# Angra_v_1_0.net
KiCad netlist of a schematic drawn in EAGLE
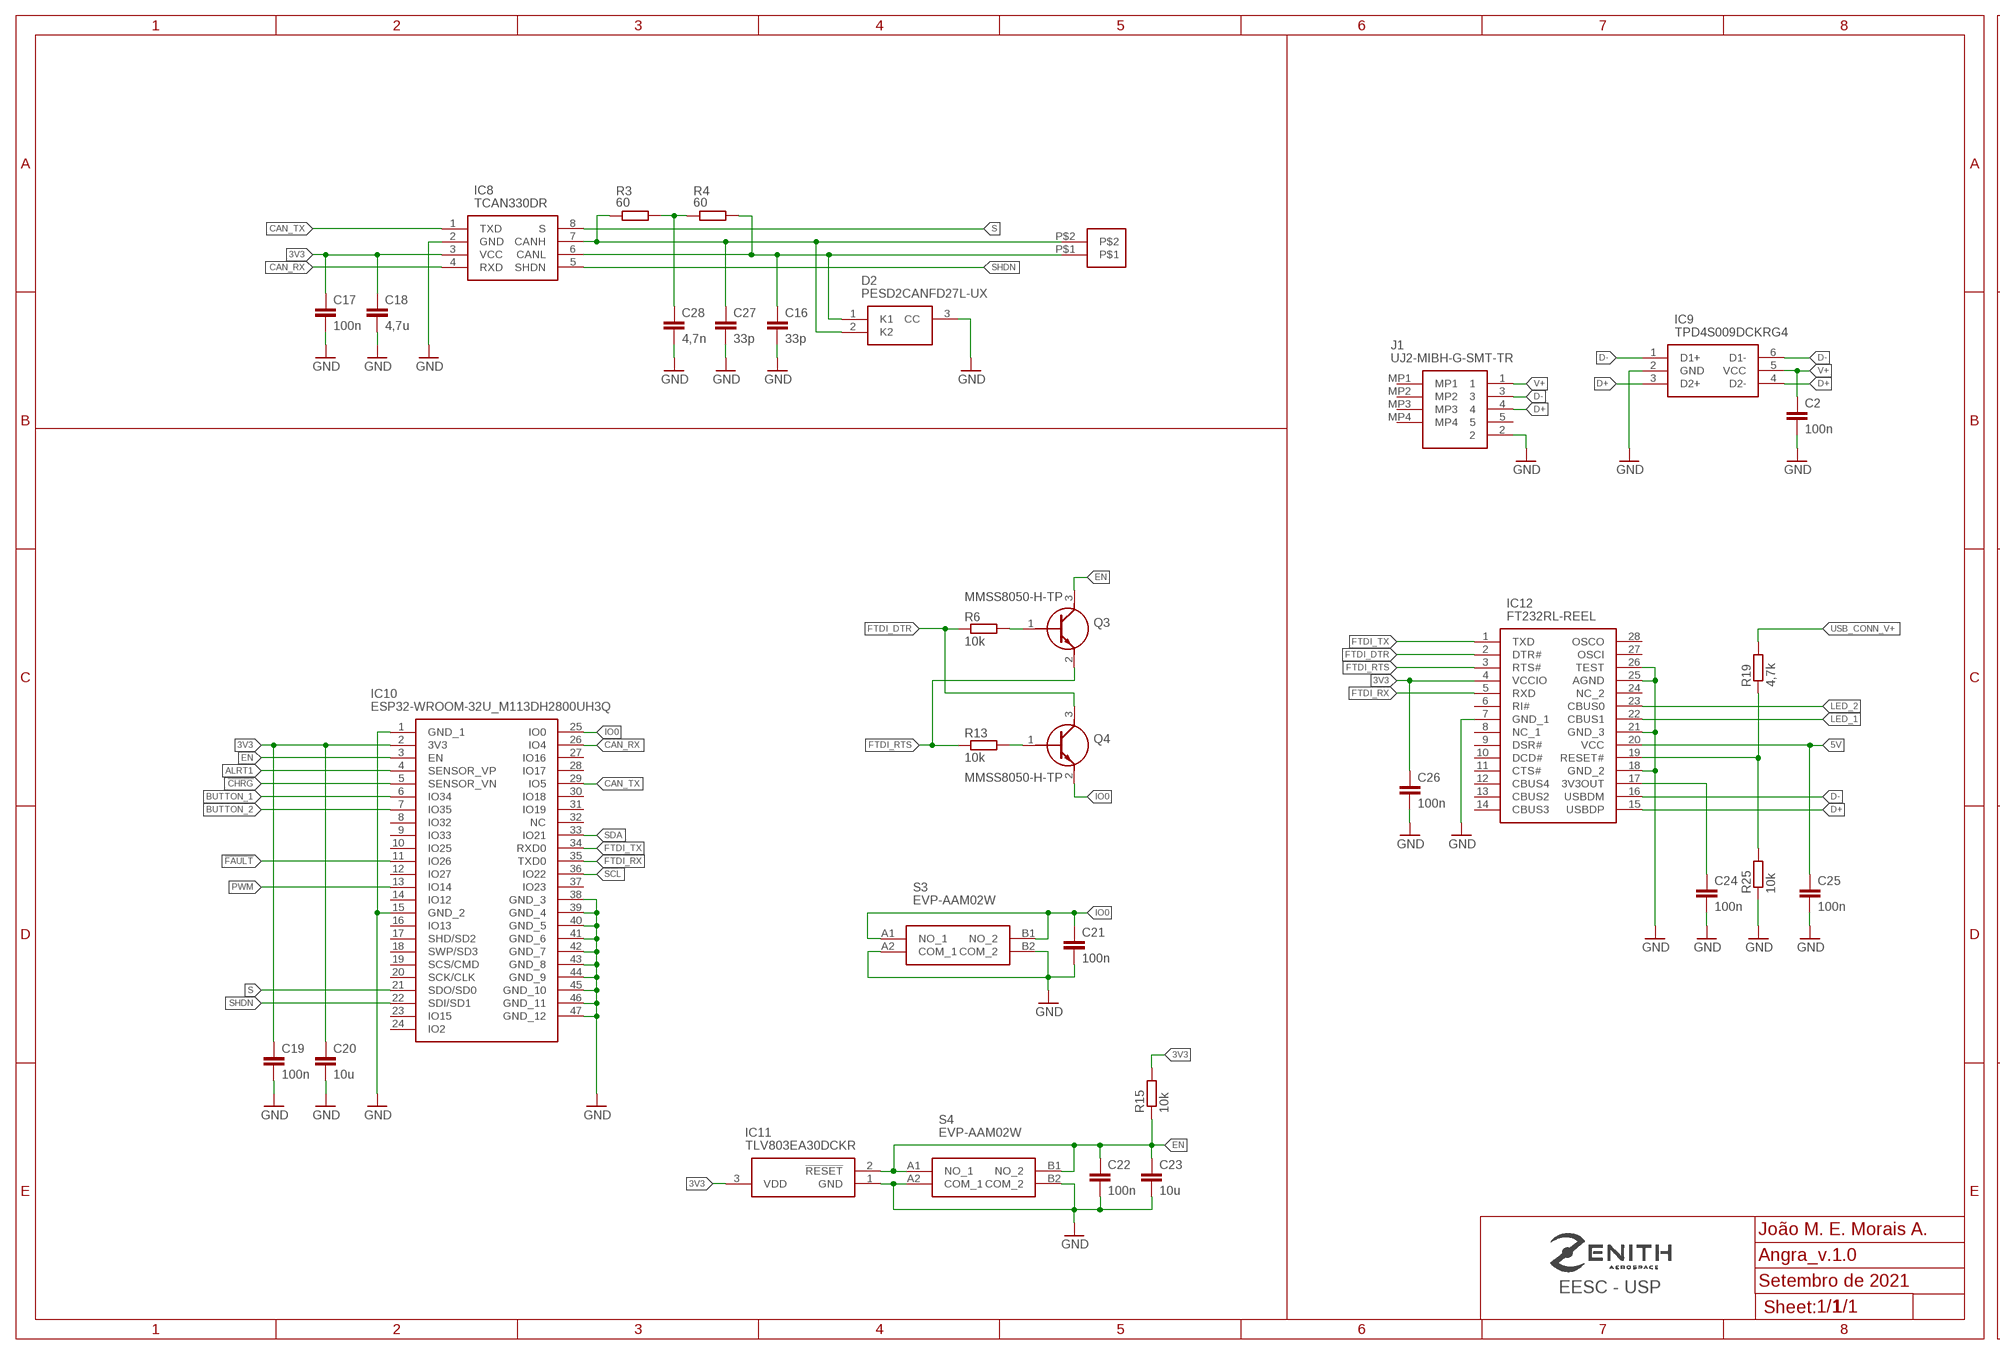
[diagram p0: schematic, sheet 1, part 1 of 2]
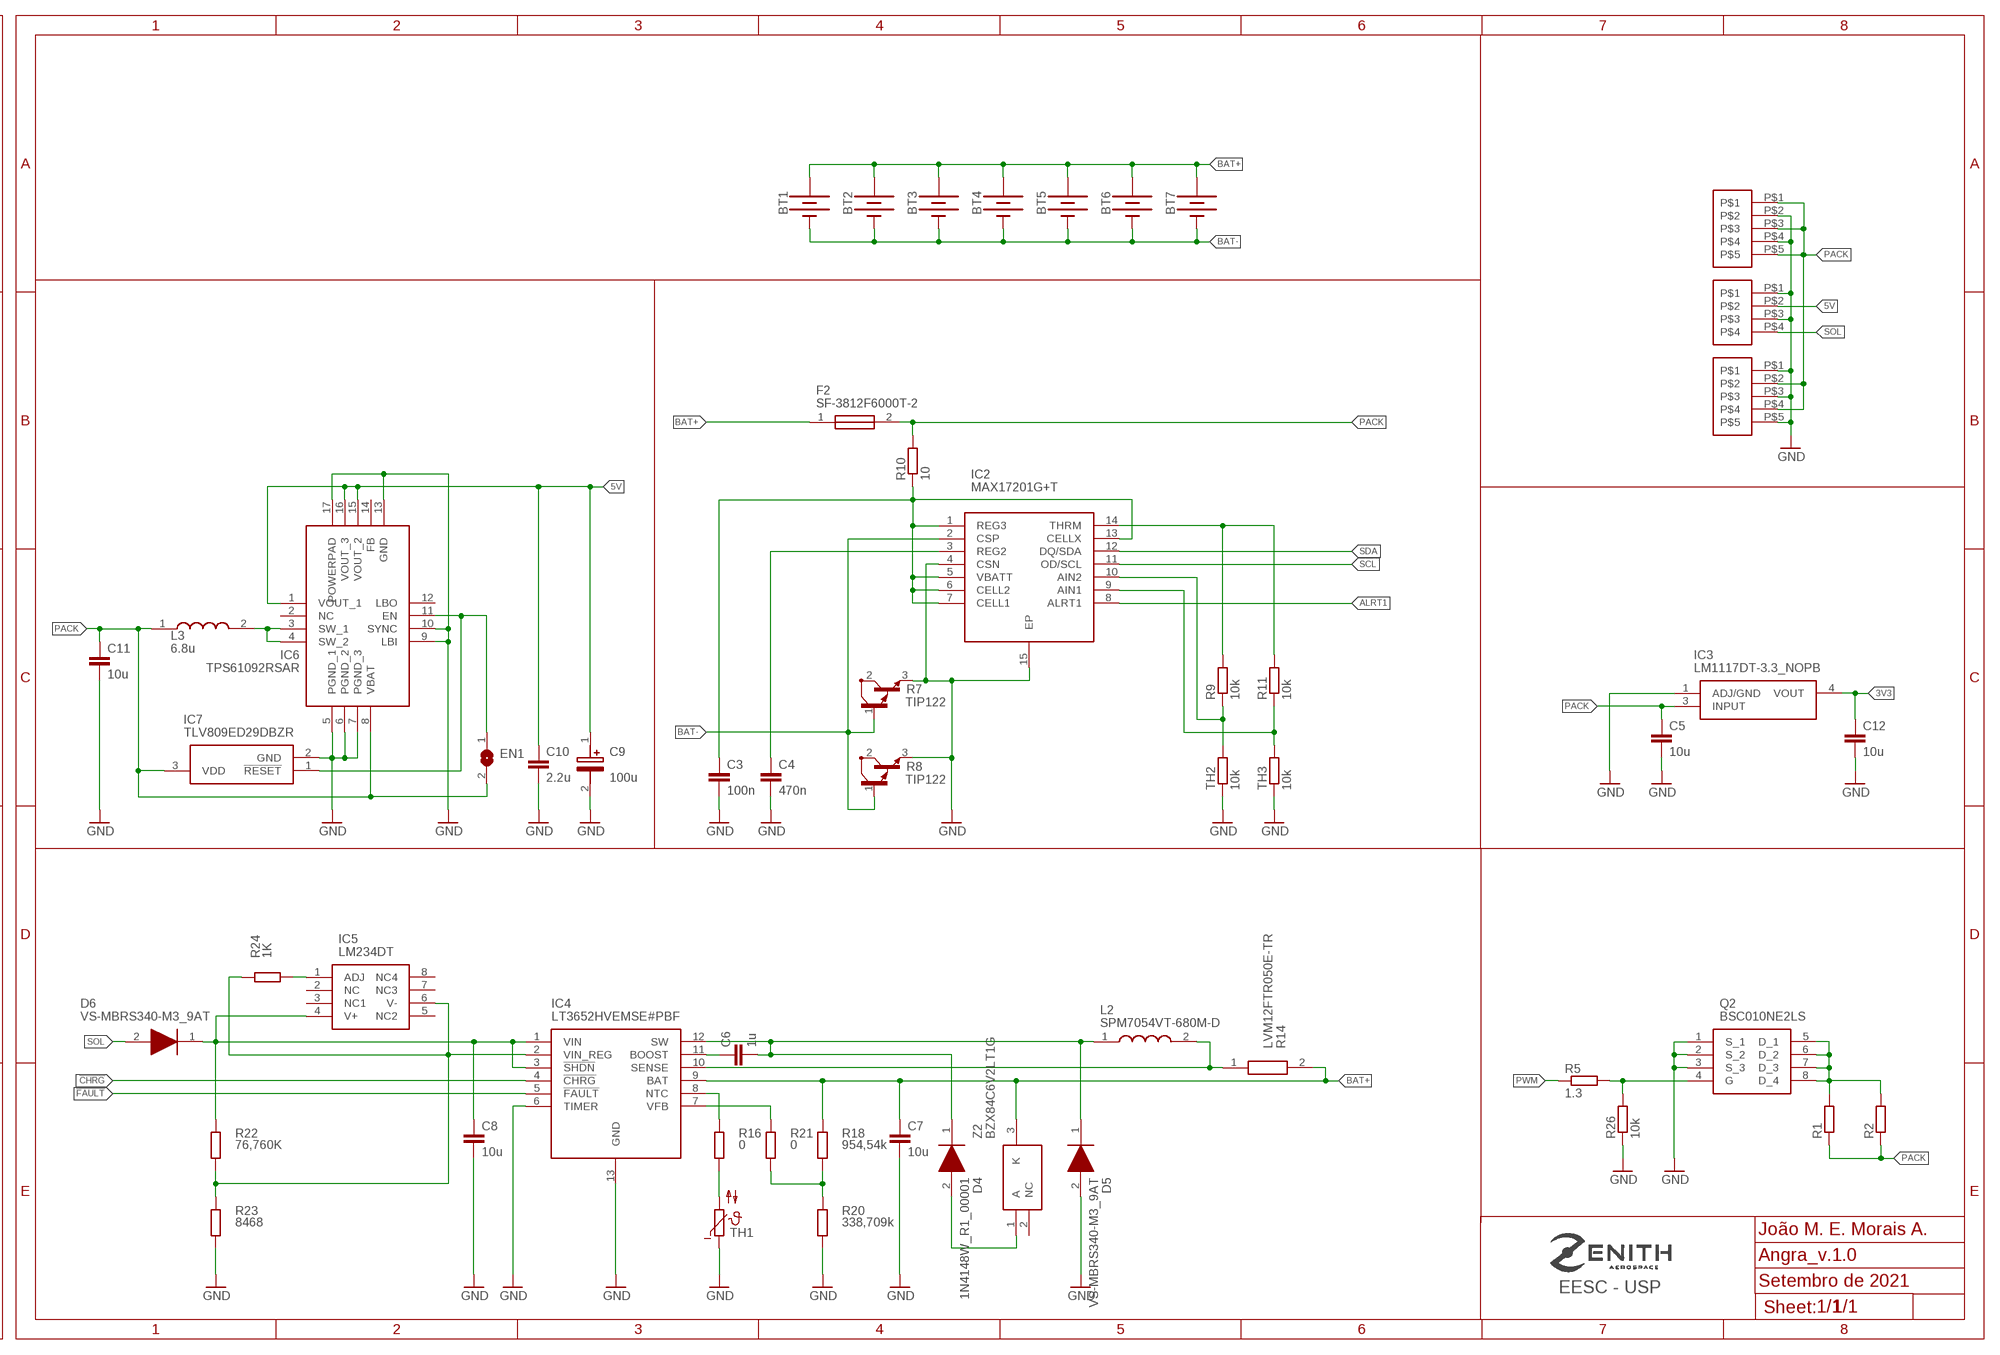
[diagram p1: schematic, sheet 1, part 2 of 2]

(export (version "E")
  (design (tool "Eeschema 10.0.6"))
  (components
    (comp (ref "BT1")
      (value "BATTERY-18650")
      (footprint "eagle-import:BATTERY_18650-HOLDER")
      (libsource (lib "eagle-import") (part "BATTERY-18650"))
    )
    (comp (ref "BT2")
      (value "BATTERY-18650")
      (footprint "eagle-import:BATTERY_18650-HOLDER")
      (libsource (lib "eagle-import") (part "BATTERY-18650"))
    )
    (comp (ref "BT3")
      (value "BATTERY-18650")
      (footprint "eagle-import:BATTERY_18650-HOLDER")
      (libsource (lib "eagle-import") (part "BATTERY-18650"))
    )
    (comp (ref "BT4")
      (value "BATTERY-18650")
      (footprint "eagle-import:BATTERY_18650-HOLDER")
      (libsource (lib "eagle-import") (part "BATTERY-18650"))
    )
    (comp (ref "BT5")
      (value "BATTERY-18650")
      (footprint "eagle-import:BATTERY_18650-HOLDER")
      (libsource (lib "eagle-import") (part "BATTERY-18650"))
    )
    (comp (ref "BT6")
      (value "BATTERY-18650")
      (footprint "eagle-import:BATTERY_18650-HOLDER")
      (libsource (lib "eagle-import") (part "BATTERY-18650"))
    )
    (comp (ref "BT7")
      (value "BATTERY-18650")
      (footprint "eagle-import:BATTERY_18650-HOLDER")
      (libsource (lib "eagle-import") (part "BATTERY-18650"))
    )
    (comp (ref "C2")
      (value "100n")
      (footprint "eagle-import:C0805")
      (libsource (lib "eagle-import") (part "C-EUC0805"))
    )
    (comp (ref "C3")
      (value "100n")
      (footprint "eagle-import:C0805")
      (libsource (lib "eagle-import") (part "C-EUC0805"))
    )
    (comp (ref "C4")
      (value "470n")
      (footprint "eagle-import:C0805")
      (libsource (lib "eagle-import") (part "C-EUC0805"))
    )
    (comp (ref "C5")
      (value "10u")
      (footprint "eagle-import:C0805")
      (libsource (lib "eagle-import") (part "C-EUC0805"))
    )
    (comp (ref "C6")
      (value "1u")
      (footprint "eagle-import:C0805")
      (libsource (lib "eagle-import") (part "C-EUC0805"))
    )
    (comp (ref "C7")
      (value "10u")
      (footprint "eagle-import:C0805")
      (libsource (lib "eagle-import") (part "C-EUC0805"))
    )
    (comp (ref "C8")
      (value "10u")
      (footprint "eagle-import:C0805")
      (libsource (lib "eagle-import") (part "C-EUC0805"))
    )
    (comp (ref "C9")
      (value "100u")
      (footprint "eagle-import:CAPPM3528X210N")
      (fields
        (field (name "MANUFACTURER_PART_NUMBER") "T598B107M004ATE045")
        (field (name "MOUSER_PART_NUMBER") "80-T598B107M004ATE45")
      )
      (libsource (lib "eagle-import") (part "T598B107M004ATE045"))
    )
    (comp (ref "C10")
      (value "2.2u")
      (footprint "eagle-import:C1206")
      (libsource (lib "eagle-import") (part "C-EUC1206"))
    )
    (comp (ref "C11")
      (value "10u")
      (footprint "eagle-import:C1206")
      (libsource (lib "eagle-import") (part "C-EUC1206"))
    )
    (comp (ref "C12")
      (value "10u")
      (footprint "eagle-import:C0805")
      (libsource (lib "eagle-import") (part "C-EUC0805"))
    )
    (comp (ref "C16")
      (value "33p")
      (footprint "eagle-import:C0805")
      (libsource (lib "eagle-import") (part "C-EUC0805"))
    )
    (comp (ref "C17")
      (value "100n")
      (footprint "eagle-import:C0805")
      (libsource (lib "eagle-import") (part "C-EUC0805"))
    )
    (comp (ref "C18")
      (value "4,7u")
      (footprint "eagle-import:C0805")
      (libsource (lib "eagle-import") (part "C-EUC0805"))
    )
    (comp (ref "C19")
      (value "100n")
      (footprint "eagle-import:C0805")
      (libsource (lib "eagle-import") (part "C-EUC0805"))
    )
    (comp (ref "C20")
      (value "10u")
      (footprint "eagle-import:C0805")
      (libsource (lib "eagle-import") (part "C-EUC0805"))
    )
    (comp (ref "C21")
      (value "100n")
      (footprint "eagle-import:C0805")
      (libsource (lib "eagle-import") (part "C-EUC0805"))
    )
    (comp (ref "C22")
      (value "100n")
      (footprint "eagle-import:C0805")
      (libsource (lib "eagle-import") (part "C-EUC0805"))
    )
    (comp (ref "C23")
      (value "10u")
      (footprint "eagle-import:C0805")
      (libsource (lib "eagle-import") (part "C-EUC0805"))
    )
    (comp (ref "C24")
      (value "100n")
      (footprint "eagle-import:C0805")
      (libsource (lib "eagle-import") (part "C-EUC0805"))
    )
    (comp (ref "C25")
      (value "100n")
      (footprint "eagle-import:C0805")
      (libsource (lib "eagle-import") (part "C-EUC0805"))
    )
    (comp (ref "C26")
      (value "100n")
      (footprint "eagle-import:C0805")
      (libsource (lib "eagle-import") (part "C-EUC0805"))
    )
    (comp (ref "C27")
      (value "33p")
      (footprint "eagle-import:C0805")
      (libsource (lib "eagle-import") (part "C-EUC0805"))
    )
    (comp (ref "C28")
      (value "4,7n")
      (footprint "eagle-import:C0805")
      (libsource (lib "eagle-import") (part "C-EUC0805"))
    )
    (comp (ref "D2")
      (value "PESD2CANFD27L-UX")
      (footprint "eagle-import:SOT65P210X110-3N")
      (fields (field (name "MOUSER_PART_NUMBER") "771-PESD2CANFD27L-UX"))
      (libsource (lib "eagle-import") (part "PESD2CANFD27L-UX"))
    )
    (comp (ref "D4")
      (value "1N4148W_R1_00001")
      (footprint "eagle-import:SOD3816X135N")
      (fields (field (name "MOUSER_PART_NUMBER") "241-1N4148W_R1_00001"))
      (libsource (lib "eagle-import") (part "1N4148W_R1_00001"))
    )
    (comp (ref "D5")
      (value "VS-MBRS340-M3_9AT")
      (footprint "eagle-import:DIOM7959X262N")
      (fields
        (field (name "MANUFACTURER_PART_NUMBER") "VS-MBRS340-M3/9AT")
        (field (name "MOUSER_PART_NUMBER") "78-VS-MBRS340-M39AT")
      )
      (libsource (lib "eagle-import") (part "VS-MBRS340-M3_9AT"))
    )
    (comp (ref "D6")
      (value "VS-MBRS340-M3_9AT")
      (footprint "eagle-import:DIOM7959X262N")
      (fields
        (field (name "MANUFACTURER_PART_NUMBER") "VS-MBRS340-M3/9AT")
        (field (name "MOUSER_PART_NUMBER") "78-VS-MBRS340-M39AT")
      )
      (libsource (lib "eagle-import") (part "VS-MBRS340-M3_9AT"))
    )
    (comp (ref "EN1")
      (value "SOLDERJUMPERREFLOW_NOPASTE")
      (footprint "eagle-import:SOLDERJUMPER_REFLOW_NOPASTE")
      (libsource (lib "eagle-import") (part "SOLDERJUMPERREFLOW_NOPASTE"))
    )
    (comp (ref "F2")
      (value "SF-3812F6000T-2")
      (footprint "eagle-import:FUSC10131X330N")
      (fields (field (name "MOUSER_PART_NUMBER") "652-SF-3812F6000T-2"))
      (libsource (lib "eagle-import") (part "SF-3812F6000T-2"))
    )
    (comp (ref "IC2")
      (value "MAX17201G+T")
      (footprint "eagle-import:SON40P300X300X80-15N")
      (fields (field (name "MOUSER_PART_NUMBER") "700-MAX17201G+T"))
      (libsource (lib "eagle-import") (part "MAX17201G+T"))
    )
    (comp (ref "IC3")
      (value "LM1117DT-3.3_NOPB")
      (footprint "eagle-import:TO228P991X238-3N")
      (fields
        (field (name "MANUFACTURER_PART_NUMBER") "LM1117DT-3.3/NOPB")
        (field (name "MOUSER_PART_NUMBER") "926-LM1117DT-3.3NOPB")
      )
      (libsource (lib "eagle-import") (part "LM1117DT-3.3_NOPB"))
    )
    (comp (ref "IC4")
      (value "LT3652HVEMSE#PBF")
      (footprint "eagle-import:SOP65P490X110-13N")
      (fields (field (name "MOUSER_PART_NUMBER") "584-LT3652HVEMSE#PBF"))
      (libsource (lib "eagle-import") (part "LT3652HVEMSE#PBF"))
    )
    (comp (ref "IC5")
      (value "LM234DT")
      (footprint "eagle-import:SOIC127P600X175-8N@1")
      (fields (field (name "MOUSER_PART_NUMBER") "511-LM234D"))
      (libsource (lib "eagle-import") (part "LM234DT"))
    )
    (comp (ref "IC6")
      (value "TPS61092RSAR")
      (footprint "eagle-import:QFN65P400X400X100-17N")
      (fields (field (name "MOUSER_PART_NUMBER") "595-TPS61092RSAR"))
      (libsource (lib "eagle-import") (part "TPS61092RSAR"))
    )
    (comp (ref "IC7")
      (value "TLV809ED29DBZR")
      (footprint "eagle-import:SOT95P237X112-3N")
      (fields (field (name "MOUSER_PART_NUMBER") "595-TLV809ED29DBZR"))
      (libsource (lib "eagle-import") (part "TLV809ED29DBZR"))
    )
    (comp (ref "IC8")
      (value "TCAN330DR")
      (footprint "eagle-import:SOIC127P600X175-8N")
      (fields (field (name "MOUSER_PART_NUMBER") "595-TCAN330DR"))
      (libsource (lib "eagle-import") (part "TCAN330DR"))
    )
    (comp (ref "IC9")
      (value "TPD4S009DCKRG4")
      (footprint "eagle-import:SOT65P210X110-6N")
      (fields (field (name "MOUSER_PART_NUMBER") "595-TPD4S009DCKRG4"))
      (libsource (lib "eagle-import") (part "TPD4S009DCKRG4"))
    )
    (comp (ref "IC10")
      (value "ESP32-WROOM-32U_M113DH2800UH3Q")
      (footprint "eagle-import:ESP32WROOM32UM113DH2800UH3Q0")
      (fields
        (field (name "MANUFACTURER_PART_NUMBER") "ESP32-WROOM-32U(M113DH2800UH3Q0)")
        (field (name "MOUSER_PART_NUMBER") "356-ES32WROOM32U16MB")
      )
      (libsource (lib "eagle-import") (part "ESP32-WROOM-32U_M113DH2800UH3Q"))
    )
    (comp (ref "IC11")
      (value "TLV803EA30DCKR")
      (footprint "eagle-import:SOT65P210X110-3N@1")
      (fields (field (name "MOUSER_PART_NUMBER") "595-TLV803EA30DCKR"))
      (libsource (lib "eagle-import") (part "TLV803EA30DCKR"))
    )
    (comp (ref "IC12")
      (value "FT232RL-REEL")
      (footprint "eagle-import:SOP65P778X200-28N")
      (fields (field (name "MOUSER_PART_NUMBER") "895-FT232RL"))
      (libsource (lib "eagle-import") (part "FT232RL-REEL"))
    )
    (comp (ref "J1")
      (value "UJ2-MIBH-G-SMT-TR")
      (footprint "eagle-import:UJ2MIBHGSMTTR")
      (fields (field (name "MOUSER_PART_NUMBER") "490-UJ2-MIBH-G-SMTTR"))
      (libsource (lib "eagle-import") (part "UJ2-MIBH-G-SMT-TR"))
    )
    (comp (ref "L2")
      (value "SPM7054VT-680M-D")
      (footprint "eagle-import:SPM7054VT")
      (fields (field (name "MOUSER_PART_NUMBER") "810-SPM7054VT-680M-D"))
      (libsource (lib "eagle-import") (part "SPM7054VT-680M-D"))
    )
    (comp (ref "L3")
      (value "6.8u")
      (footprint "eagle-import:INDPM4040X210N")
      (fields
        (field (name "MANUFACTURER_PART_NUMBER") "TYA40206R8M-10")
        (field (name "MOUSER_PART_NUMBER") "739-TYA40206R8M-10")
      )
      (libsource (lib "eagle-import") (part "TYA40206R8M-10"))
    )
    (comp (ref "Q2")
      (value "BSC010NE2LS")
      (footprint "eagle-import:PG-TDSON-8")
      (fields (field (name "MOUSER_PART_NUMBER") "726-BSC010NE2LS"))
      (libsource (lib "eagle-import") (part "BSC010NE2LS"))
    )
    (comp (ref "Q3")
      (value "MMSS8050-H-TP")
      (footprint "eagle-import:SI2305TP")
      (fields (field (name "MOUSER_PART_NUMBER") "833-MMSS8050-H-TP"))
      (libsource (lib "eagle-import") (part "MMSS8050-H-TP"))
    )
    (comp (ref "Q4")
      (value "MMSS8050-H-TP")
      (footprint "eagle-import:SI2305TP")
      (fields (field (name "MOUSER_PART_NUMBER") "833-MMSS8050-H-TP"))
      (libsource (lib "eagle-import") (part "MMSS8050-H-TP"))
    )
    (comp (ref "R1")
      (value "R-EU_0207/7")
      (footprint "eagle-import:0207_7")
      (libsource (lib "eagle-import") (part "R-EU_0207/7"))
    )
    (comp (ref "R2")
      (value "R-EU_0207/7")
      (footprint "eagle-import:0207_7")
      (libsource (lib "eagle-import") (part "R-EU_0207/7"))
    )
    (comp (ref "R3")
      (value "60")
      (footprint "eagle-import:R0805")
      (libsource (lib "eagle-import") (part "R-EU_R0805"))
    )
    (comp (ref "R4")
      (value "60")
      (footprint "eagle-import:R0805")
      (libsource (lib "eagle-import") (part "R-EU_R0805"))
    )
    (comp (ref "R5")
      (value "1.3")
      (footprint "eagle-import:R0805")
      (libsource (lib "eagle-import") (part "R-EU_R0805"))
    )
    (comp (ref "R6")
      (value "10k")
      (footprint "eagle-import:R0805")
      (libsource (lib "eagle-import") (part "R-EU_R0805"))
    )
    (comp (ref "R7")
      (value "TIP122")
      (footprint "eagle-import:TO220")
      (libsource (lib "eagle-import") (part "TIP122"))
    )
    (comp (ref "R8")
      (value "TIP122")
      (footprint "eagle-import:TO220")
      (libsource (lib "eagle-import") (part "TIP122"))
    )
    (comp (ref "R9")
      (value "10k")
      (footprint "eagle-import:R0805")
      (libsource (lib "eagle-import") (part "R-EU_R0805"))
    )
    (comp (ref "R10")
      (value "10")
      (footprint "eagle-import:R0805")
      (libsource (lib "eagle-import") (part "R-EU_R0805"))
    )
    (comp (ref "R11")
      (value "10k")
      (footprint "eagle-import:R0805")
      (libsource (lib "eagle-import") (part "R-EU_R0805"))
    )
    (comp (ref "R13")
      (value "10k")
      (footprint "eagle-import:R0805")
      (libsource (lib "eagle-import") (part "R-EU_R0805"))
    )
    (comp (ref "R14")
      (value "LVM12FTR050E-TR")
      (footprint "eagle-import:RESC3016X70N")
      (fields (field (name "MOUSER_PART_NUMBER") "588-LVM12FTR050E-TR"))
      (libsource (lib "eagle-import") (part "LVM12FTR050E-TR"))
    )
    (comp (ref "R15")
      (value "10k")
      (footprint "eagle-import:R0805")
      (libsource (lib "eagle-import") (part "R-EU_R0805"))
    )
    (comp (ref "R16")
      (value "0")
      (footprint "eagle-import:R0805")
      (libsource (lib "eagle-import") (part "R-EU_R0805"))
    )
    (comp (ref "R18")
      (value "954,54k")
      (footprint "eagle-import:R0805")
      (libsource (lib "eagle-import") (part "R-EU_R0805"))
    )
    (comp (ref "R19")
      (value "4,7k")
      (footprint "eagle-import:R0805")
      (libsource (lib "eagle-import") (part "R-EU_R0805"))
    )
    (comp (ref "R20")
      (value "338,709k")
      (footprint "eagle-import:R0805")
      (libsource (lib "eagle-import") (part "R-EU_R0805"))
    )
    (comp (ref "R21")
      (value "0")
      (footprint "eagle-import:R0805")
      (libsource (lib "eagle-import") (part "R-EU_R0805"))
    )
    (comp (ref "R22")
      (value "76,760K")
      (footprint "eagle-import:R0805")
      (libsource (lib "eagle-import") (part "R-EU_R0805"))
    )
    (comp (ref "R23")
      (value "8468")
      (footprint "eagle-import:R0805")
      (libsource (lib "eagle-import") (part "R-EU_R0805"))
    )
    (comp (ref "R24")
      (value "1K")
      (footprint "eagle-import:R0805")
      (libsource (lib "eagle-import") (part "R-EU_R0805"))
    )
    (comp (ref "R25")
      (value "10k")
      (footprint "eagle-import:R0805")
      (libsource (lib "eagle-import") (part "R-EU_R0805"))
    )
    (comp (ref "R26")
      (value "10k")
      (footprint "eagle-import:R0805")
      (libsource (lib "eagle-import") (part "R-EU_R0805"))
    )
    (comp (ref "S3")
      (value "EVP-AAM02W")
      (footprint "eagle-import:EVPAAM02W")
      (fields (field (name "MOUSER_PART_NUMBER") "667-EVP-AAM02W"))
      (libsource (lib "eagle-import") (part "EVP-AAM02W"))
    )
    (comp (ref "S4")
      (value "EVP-AAM02W")
      (footprint "eagle-import:EVPAAM02W")
      (fields (field (name "MOUSER_PART_NUMBER") "667-EVP-AAM02W"))
      (libsource (lib "eagle-import") (part "EVP-AAM02W"))
    )
    (comp (ref "TH1")
      (value "NTC640")
      (footprint "eagle-import:P640")
      (libsource (lib "eagle-import") (part "NTC640"))
    )
    (comp (ref "TH2")
      (value "10k")
      (footprint "eagle-import:0207_7")
      (libsource (lib "eagle-import") (part "R-EU_0207/7"))
    )
    (comp (ref "TH3")
      (value "10k")
      (footprint "eagle-import:0207_7")
      (libsource (lib "eagle-import") (part "R-EU_0207/7"))
    )
    (comp (ref "U$1")
      (value "S02B-XASS-1")
      (footprint "eagle-import:S02B-XASS-1")
      (libsource (lib "eagle-import") (part "S02B-XASS-1"))
    )
    (comp (ref "U$2")
      (value "S05B-XASS-1")
      (footprint "eagle-import:S05B-XASS-1")
      (libsource (lib "eagle-import") (part "S05B-XASS-1"))
    )
    (comp (ref "U$3")
      (value "S05B-XASS-1")
      (footprint "eagle-import:S05B-XASS-1")
      (libsource (lib "eagle-import") (part "S05B-XASS-1"))
    )
    (comp (ref "U$4")
      (value "S04B-XASS-1")
      (footprint "eagle-import:S04B-XASS-1")
      (libsource (lib "eagle-import") (part "S04B-XASS-1"))
    )
    (comp (ref "Z2")
      (value "BZX84C6V2LT1G")
      (footprint "eagle-import:SOT96P237X111-3N")
      (fields (field (name "MOUSER_PART_NUMBER") "863-BZX84C6V2LT1G"))
      (libsource (lib "eagle-import") (part "BZX84C6V2LT1G"))
    )
  )
  (nets
    (net (code "1") (name "/~{CHRG}") (class "Default")
      (node (ref "IC10") (pin "5") (pinfunction "SENSOR_VN_5") (pintype "bidirectional"))
      (node (ref "IC4") (pin "4") (pinfunction "~{CHRG}_4") (pintype "bidirectional"))
    )
    (net (code "2") (name "/~{FAULT}") (class "Default")
      (node (ref "IC10") (pin "11") (pinfunction "IO26_11") (pintype "bidirectional"))
      (node (ref "IC4") (pin "5") (pinfunction "~{FAULT}_5") (pintype "bidirectional"))
    )
    (net (code "3") (name "3V3") (class "Default")
      (node (ref "C12") (pin "1") (pinfunction "1_1") (pintype "passive"))
      (node (ref "C17") (pin "1") (pinfunction "1_1") (pintype "passive"))
      (node (ref "C18") (pin "1") (pinfunction "1_1") (pintype "passive"))
      (node (ref "C19") (pin "1") (pinfunction "1_1") (pintype "passive"))
      (node (ref "C20") (pin "1") (pinfunction "1_1") (pintype "passive"))
      (node (ref "C26") (pin "1") (pinfunction "1_1") (pintype "passive"))
      (node (ref "IC10") (pin "2") (pinfunction "3V3_2") (pintype "bidirectional"))
      (node (ref "IC11") (pin "3") (pinfunction "VDD_3") (pintype "bidirectional"))
      (node (ref "IC12") (pin "4") (pinfunction "VCCIO_4") (pintype "bidirectional"))
      (node (ref "IC3") (pin "4") (pinfunction "VOUT_4") (pintype "output"))
      (node (ref "IC8") (pin "3") (pinfunction "VCC_3") (pintype "bidirectional"))
      (node (ref "R15") (pin "2") (pinfunction "2_2") (pintype "passive"))
    )
    (net (code "4") (name "5V") (class "Default")
      (node (ref "C10") (pin "1") (pinfunction "1_1") (pintype "passive"))
      (node (ref "C25") (pin "1") (pinfunction "1_1") (pintype "passive"))
      (node (ref "C9") (pin "1") (pinfunction "+_1") (pintype "bidirectional"))
      (node (ref "IC12") (pin "20") (pinfunction "VCC_20") (pintype "bidirectional"))
      (node (ref "IC6") (pin "1") (pinfunction "VOUT_1_1") (pintype "bidirectional"))
      (node (ref "IC6") (pin "15") (pinfunction "VOUT_2_15") (pintype "bidirectional"))
      (node (ref "IC6") (pin "16") (pinfunction "VOUT_3_16") (pintype "bidirectional"))
      (node (ref "U$4") (pin "P$2") (pinfunction "P$2_P$2") (pintype "bidirectional"))
    )
    (net (code "5") (name "ALRT1") (class "Default")
      (node (ref "IC10") (pin "4") (pinfunction "SENSOR_VP_4") (pintype "bidirectional"))
      (node (ref "IC2") (pin "8") (pinfunction "ALRT1_8") (pintype "bidirectional"))
    )
    (net (code "6") (name "BAT+") (class "Default")
      (node (ref "BT1") (pin "PWR@1") (pinfunction "+_PWR@1") (pintype "power_in"))
      (node (ref "BT2") (pin "PWR@1") (pinfunction "+_PWR@1") (pintype "power_in"))
      (node (ref "BT3") (pin "PWR@1") (pinfunction "+_PWR@1") (pintype "power_in"))
      (node (ref "BT4") (pin "PWR@1") (pinfunction "+_PWR@1") (pintype "power_in"))
      (node (ref "BT5") (pin "PWR@1") (pinfunction "+_PWR@1") (pintype "power_in"))
      (node (ref "BT6") (pin "PWR@1") (pinfunction "+_PWR@1") (pintype "power_in"))
      (node (ref "BT7") (pin "PWR@1") (pinfunction "+_PWR@1") (pintype "power_in"))
      (node (ref "C7") (pin "1") (pinfunction "1_1") (pintype "passive"))
      (node (ref "F2") (pin "1") (pinfunction "1_1") (pintype "bidirectional"))
      (node (ref "IC4") (pin "9") (pinfunction "BAT_9") (pintype "bidirectional"))
      (node (ref "R14") (pin "2") (pinfunction "2_2") (pintype "bidirectional"))
      (node (ref "R18") (pin "1") (pinfunction "1_1") (pintype "passive"))
      (node (ref "Z2") (pin "3") (pinfunction "K_3") (pintype "bidirectional"))
    )
    (net (code "7") (name "BAT-") (class "Default")
      (node (ref "BT1") (pin "GND@1") (pinfunction "-_GND@1") (pintype "power_in"))
      (node (ref "BT2") (pin "GND@1") (pinfunction "-_GND@1") (pintype "power_in"))
      (node (ref "BT3") (pin "GND@1") (pinfunction "-_GND@1") (pintype "power_in"))
      (node (ref "BT4") (pin "GND@1") (pinfunction "-_GND@1") (pintype "power_in"))
      (node (ref "BT5") (pin "GND@1") (pinfunction "-_GND@1") (pintype "power_in"))
      (node (ref "BT6") (pin "GND@1") (pinfunction "-_GND@1") (pintype "power_in"))
      (node (ref "BT7") (pin "GND@1") (pinfunction "-_GND@1") (pintype "power_in"))
      (node (ref "IC2") (pin "2") (pinfunction "CSP_2") (pintype "bidirectional"))
      (node (ref "R7") (pin "1") (pinfunction "B_1") (pintype "passive"))
      (node (ref "R8") (pin "1") (pinfunction "B_1") (pintype "passive"))
    )
    (net (code "8") (name "BUTTON_1") (class "Default")
      (node (ref "IC10") (pin "6") (pinfunction "IO34_6") (pintype "bidirectional"))
    )
    (net (code "9") (name "BUTTON_2") (class "Default")
      (node (ref "IC10") (pin "7") (pinfunction "IO35_7") (pintype "bidirectional"))
    )
    (net (code "10") (name "CAN_RX") (class "Default")
      (node (ref "IC10") (pin "26") (pinfunction "IO4_26") (pintype "bidirectional"))
      (node (ref "IC8") (pin "4") (pinfunction "RXD_4") (pintype "bidirectional"))
    )
    (net (code "11") (name "CAN_TX") (class "Default")
      (node (ref "IC10") (pin "29") (pinfunction "IO5_29") (pintype "bidirectional"))
      (node (ref "IC8") (pin "1") (pinfunction "TXD_1") (pintype "bidirectional"))
    )
    (net (code "12") (name "D+") (class "Default")
      (node (ref "IC12") (pin "15") (pinfunction "USBDP_15") (pintype "bidirectional"))
      (node (ref "IC9") (pin "3") (pinfunction "D2+_3") (pintype "bidirectional"))
      (node (ref "IC9") (pin "4") (pinfunction "D2-_4") (pintype "bidirectional"))
      (node (ref "J1") (pin "4") (pinfunction "4_4") (pintype "bidirectional"))
    )
    (net (code "13") (name "D-") (class "Default")
      (node (ref "IC12") (pin "16") (pinfunction "USBDM_16") (pintype "bidirectional"))
      (node (ref "IC9") (pin "1") (pinfunction "D1+_1") (pintype "bidirectional"))
      (node (ref "IC9") (pin "6") (pinfunction "D1-_6") (pintype "bidirectional"))
      (node (ref "J1") (pin "3") (pinfunction "3_3") (pintype "bidirectional"))
    )
    (net (code "14") (name "EN") (class "Default")
      (node (ref "C22") (pin "1") (pinfunction "1_1") (pintype "passive"))
      (node (ref "C23") (pin "1") (pinfunction "1_1") (pintype "passive"))
      (node (ref "IC10") (pin "3") (pinfunction "EN_3") (pintype "bidirectional"))
      (node (ref "IC11") (pin "2") (pinfunction "~{RESET}_2") (pintype "bidirectional"))
      (node (ref "Q3") (pin "3") (pinfunction "C_3") (pintype "bidirectional"))
      (node (ref "R15") (pin "1") (pinfunction "1_1") (pintype "passive"))
      (node (ref "S4") (pin "A1") (pinfunction "NO_1_A1") (pintype "bidirectional"))
      (node (ref "S4") (pin "B1") (pinfunction "NO_2_B1") (pintype "bidirectional"))
    )
    (net (code "15") (name "FTDI_DTR") (class "Default")
      (node (ref "IC12") (pin "2") (pinfunction "DTR#_2") (pintype "bidirectional"))
      (node (ref "Q4") (pin "3") (pinfunction "C_3") (pintype "bidirectional"))
      (node (ref "R6") (pin "1") (pinfunction "1_1") (pintype "passive"))
    )
    (net (code "16") (name "FTDI_RTS") (class "Default")
      (node (ref "IC12") (pin "3") (pinfunction "RTS#_3") (pintype "bidirectional"))
      (node (ref "Q3") (pin "2") (pinfunction "E_2") (pintype "bidirectional"))
      (node (ref "R13") (pin "1") (pinfunction "1_1") (pintype "passive"))
    )
    (net (code "17") (name "FTDI_RX") (class "Default")
      (node (ref "IC10") (pin "35") (pinfunction "TXD0_35") (pintype "bidirectional"))
      (node (ref "IC12") (pin "5") (pinfunction "RXD_5") (pintype "bidirectional"))
    )
    (net (code "18") (name "FTDI_TX") (class "Default")
      (node (ref "IC10") (pin "34") (pinfunction "RXD0_34") (pintype "bidirectional"))
      (node (ref "IC12") (pin "1") (pinfunction "TXD_1") (pintype "bidirectional"))
    )
    (net (code "19") (name "GND") (class "Default")
      (node (ref "C10") (pin "2") (pinfunction "2_2") (pintype "passive"))
      (node (ref "C11") (pin "2") (pinfunction "2_2") (pintype "passive"))
      (node (ref "C12") (pin "2") (pinfunction "2_2") (pintype "passive"))
      (node (ref "C16") (pin "2") (pinfunction "2_2") (pintype "passive"))
      (node (ref "C17") (pin "2") (pinfunction "2_2") (pintype "passive"))
      (node (ref "C18") (pin "2") (pinfunction "2_2") (pintype "passive"))
      (node (ref "C19") (pin "2") (pinfunction "2_2") (pintype "passive"))
      (node (ref "C2") (pin "2") (pinfunction "2_2") (pintype "passive"))
      (node (ref "C20") (pin "2") (pinfunction "2_2") (pintype "passive"))
      (node (ref "C21") (pin "2") (pinfunction "2_2") (pintype "passive"))
      (node (ref "C22") (pin "2") (pinfunction "2_2") (pintype "passive"))
      (node (ref "C23") (pin "2") (pinfunction "2_2") (pintype "passive"))
      (node (ref "C24") (pin "2") (pinfunction "2_2") (pintype "passive"))
      (node (ref "C25") (pin "2") (pinfunction "2_2") (pintype "passive"))
      (node (ref "C26") (pin "2") (pinfunction "2_2") (pintype "passive"))
      (node (ref "C27") (pin "2") (pinfunction "2_2") (pintype "passive"))
      (node (ref "C28") (pin "2") (pinfunction "2_2") (pintype "passive"))
      (node (ref "C3") (pin "2") (pinfunction "2_2") (pintype "passive"))
      (node (ref "C4") (pin "2") (pinfunction "2_2") (pintype "passive"))
      (node (ref "C5") (pin "2") (pinfunction "2_2") (pintype "passive"))
      (node (ref "C7") (pin "2") (pinfunction "2_2") (pintype "passive"))
      (node (ref "C8") (pin "2") (pinfunction "2_2") (pintype "passive"))
      (node (ref "C9") (pin "2") (pinfunction "-_2") (pintype "bidirectional"))
      (node (ref "D2") (pin "3") (pinfunction "CC_3") (pintype "bidirectional"))
      (node (ref "D5") (pin "2") (pinfunction "A_2") (pintype "bidirectional"))
      (node (ref "IC10") (pin "1") (pinfunction "GND_1_1") (pintype "bidirectional"))
      (node (ref "IC10") (pin "15") (pinfunction "GND_2_15") (pintype "bidirectional"))
      (node (ref "IC10") (pin "38") (pinfunction "GND_3_38") (pintype "bidirectional"))
      (node (ref "IC10") (pin "39") (pinfunction "GND_4_39") (pintype "bidirectional"))
      (node (ref "IC10") (pin "40") (pinfunction "GND_5_40") (pintype "bidirectional"))
      (node (ref "IC10") (pin "41") (pinfunction "GND_6_41") (pintype "bidirectional"))
      (node (ref "IC10") (pin "42") (pinfunction "GND_7_42") (pintype "bidirectional"))
      (node (ref "IC10") (pin "43") (pinfunction "GND_8_43") (pintype "bidirectional"))
      (node (ref "IC10") (pin "44") (pinfunction "GND_9_44") (pintype "bidirectional"))
      (node (ref "IC10") (pin "45") (pinfunction "GND_10_45") (pintype "bidirectional"))
      (node (ref "IC10") (pin "46") (pinfunction "GND_11_46") (pintype "bidirectional"))
      (node (ref "IC10") (pin "47") (pinfunction "GND_12_47") (pintype "bidirectional"))
      (node (ref "IC11") (pin "1") (pinfunction "GND_1") (pintype "bidirectional"))
      (node (ref "IC12") (pin "18") (pinfunction "GND_2_18") (pintype "bidirectional"))
      (node (ref "IC12") (pin "21") (pinfunction "GND_3_21") (pintype "bidirectional"))
      (node (ref "IC12") (pin "25") (pinfunction "AGND_25") (pintype "bidirectional"))
      (node (ref "IC12") (pin "26") (pinfunction "TEST_26") (pintype "bidirectional"))
      (node (ref "IC12") (pin "7") (pinfunction "GND_1_7") (pintype "bidirectional"))
      (node (ref "IC2") (pin "15") (pinfunction "EP_15") (pintype "bidirectional"))
      (node (ref "IC2") (pin "4") (pinfunction "CSN_4") (pintype "bidirectional"))
      (node (ref "IC3") (pin "1") (pinfunction "ADJ/GND_1") (pintype "power_in"))
      (node (ref "IC4") (pin "13") (pinfunction "GND_13") (pintype "bidirectional"))
      (node (ref "IC4") (pin "6") (pinfunction "TIMER_6") (pintype "bidirectional"))
      (node (ref "IC6") (pin "10") (pinfunction "SYNC_10") (pintype "bidirectional"))
      (node (ref "IC6") (pin "13") (pinfunction "GND_13") (pintype "bidirectional"))
      (node (ref "IC6") (pin "17") (pinfunction "POWERPAD_17") (pintype "bidirectional"))
      (node (ref "IC6") (pin "5") (pinfunction "PGND_1_5") (pintype "bidirectional"))
      (node (ref "IC6") (pin "6") (pinfunction "PGND_2_6") (pintype "bidirectional"))
      (node (ref "IC6") (pin "7") (pinfunction "PGND_3_7") (pintype "bidirectional"))
      (node (ref "IC6") (pin "9") (pinfunction "LBI_9") (pintype "bidirectional"))
      (node (ref "IC7") (pin "2") (pinfunction "GND_2") (pintype "bidirectional"))
      (node (ref "IC8") (pin "2") (pinfunction "GND_2") (pintype "bidirectional"))
      (node (ref "IC9") (pin "2") (pinfunction "GND_2") (pintype "bidirectional"))
      (node (ref "J1") (pin "2") (pinfunction "2_2") (pintype "bidirectional"))
      (node (ref "Q2") (pin "1") (pinfunction "S_1_1") (pintype "bidirectional"))
      (node (ref "Q2") (pin "2") (pinfunction "S_2_2") (pintype "bidirectional"))
      (node (ref "Q2") (pin "3") (pinfunction "S_3_3") (pintype "bidirectional"))
      (node (ref "R20") (pin "2") (pinfunction "2_2") (pintype "passive"))
      (node (ref "R23") (pin "2") (pinfunction "2_2") (pintype "passive"))
      (node (ref "R25") (pin "1") (pinfunction "1_1") (pintype "passive"))
      (node (ref "R26") (pin "1") (pinfunction "1_1") (pintype "passive"))
      (node (ref "R7") (pin "3") (pinfunction "E_3") (pintype "passive"))
      (node (ref "R8") (pin "3") (pinfunction "E_3") (pintype "passive"))
      (node (ref "S3") (pin "A2") (pinfunction "COM_1_A2") (pintype "bidirectional"))
      (node (ref "S3") (pin "B2") (pinfunction "COM_2_B2") (pintype "bidirectional"))
      (node (ref "S4") (pin "A2") (pinfunction "COM_1_A2") (pintype "bidirectional"))
      (node (ref "S4") (pin "B2") (pinfunction "COM_2_B2") (pintype "bidirectional"))
      (node (ref "TH1") (pin "1") (pinfunction "1_1") (pintype "passive"))
      (node (ref "TH2") (pin "1") (pinfunction "1_1") (pintype "passive"))
      (node (ref "TH3") (pin "1") (pinfunction "1_1") (pintype "passive"))
      (node (ref "U$2") (pin "P$2") (pinfunction "P$2_P$2") (pintype "bidirectional"))
      (node (ref "U$2") (pin "P$4") (pinfunction "P$4_P$4") (pintype "bidirectional"))
      (node (ref "U$3") (pin "P$1") (pinfunction "P$1_P$1") (pintype "bidirectional"))
      (node (ref "U$3") (pin "P$3") (pinfunction "P$3_P$3") (pintype "bidirectional"))
      (node (ref "U$3") (pin "P$5") (pinfunction "P$5_P$5") (pintype "bidirectional"))
      (node (ref "U$4") (pin "P$1") (pinfunction "P$1_P$1") (pintype "bidirectional"))
      (node (ref "U$4") (pin "P$3") (pinfunction "P$3_P$3") (pintype "bidirectional"))
    )
    (net (code "20") (name "IO0") (class "Default")
      (node (ref "C21") (pin "1") (pinfunction "1_1") (pintype "passive"))
      (node (ref "IC10") (pin "25") (pinfunction "IO0_25") (pintype "bidirectional"))
      (node (ref "Q4") (pin "2") (pinfunction "E_2") (pintype "bidirectional"))
      (node (ref "S3") (pin "A1") (pinfunction "NO_1_A1") (pintype "bidirectional"))
      (node (ref "S3") (pin "B1") (pinfunction "NO_2_B1") (pintype "bidirectional"))
    )
    (net (code "21") (name "LED_1") (class "Default")
      (node (ref "IC12") (pin "22") (pinfunction "CBUS1_22") (pintype "bidirectional"))
    )
    (net (code "22") (name "LED_2") (class "Default")
      (node (ref "IC12") (pin "23") (pinfunction "CBUS0_23") (pintype "bidirectional"))
    )
    (net (code "23") (name "Net-(C28-Pad1)") (class "Default")
      (node (ref "C28") (pin "1") (pinfunction "1_1") (pintype "passive"))
      (node (ref "R3") (pin "1") (pinfunction "1_1") (pintype "passive"))
      (node (ref "R4") (pin "2") (pinfunction "2_2") (pintype "passive"))
    )
    (net (code "24") (name "Net-(D2-K1)") (class "Default")
      (node (ref "C16") (pin "1") (pinfunction "1_1") (pintype "passive"))
      (node (ref "D2") (pin "1") (pinfunction "K1_1") (pintype "bidirectional"))
      (node (ref "IC8") (pin "6") (pinfunction "CANL_6") (pintype "bidirectional"))
      (node (ref "R4") (pin "1") (pinfunction "1_1") (pintype "passive"))
      (node (ref "U$1") (pin "P$1") (pinfunction "P$1_P$1") (pintype "bidirectional"))
    )
    (net (code "25") (name "Net-(D2-K2)") (class "Default")
      (node (ref "C27") (pin "1") (pinfunction "1_1") (pintype "passive"))
      (node (ref "D2") (pin "2") (pinfunction "K2_2") (pintype "bidirectional"))
      (node (ref "IC8") (pin "7") (pinfunction "CANH_7") (pintype "bidirectional"))
      (node (ref "R3") (pin "2") (pinfunction "2_2") (pintype "passive"))
      (node (ref "U$1") (pin "P$2") (pinfunction "P$2_P$2") (pintype "bidirectional"))
    )
    (net (code "26") (name "Net-(D4-A)") (class "Default")
      (node (ref "D4") (pin "2") (pinfunction "A_2") (pintype "bidirectional"))
      (node (ref "Z2") (pin "1") (pinfunction "A_1") (pintype "bidirectional"))
    )
    (net (code "27") (name "Net-(D4-K)") (class "Default")
      (node (ref "C6") (pin "2") (pinfunction "2_2") (pintype "passive"))
      (node (ref "D4") (pin "1") (pinfunction "K_1") (pintype "bidirectional"))
      (node (ref "D5") (pin "1") (pinfunction "K_1") (pintype "bidirectional"))
      (node (ref "IC4") (pin "12") (pinfunction "SW_12") (pintype "bidirectional"))
      (node (ref "L2") (pin "1") (pinfunction "1_1") (pintype "bidirectional"))
    )
    (net (code "28") (name "Net-(D6-K)") (class "Default")
      (node (ref "C8") (pin "1") (pinfunction "1_1") (pintype "passive"))
      (node (ref "D6") (pin "1") (pinfunction "K_1") (pintype "bidirectional"))
      (node (ref "IC4") (pin "1") (pinfunction "VIN_1") (pintype "bidirectional"))
      (node (ref "IC4") (pin "3") (pinfunction "~{SHDN}_3") (pintype "bidirectional"))
      (node (ref "IC5") (pin "4") (pinfunction "V+_4") (pintype "bidirectional"))
      (node (ref "R22") (pin "1") (pinfunction "1_1") (pintype "passive"))
    )
    (net (code "29") (name "Net-(IC2-AIN1)") (class "Default")
      (node (ref "IC2") (pin "9") (pinfunction "AIN1_9") (pintype "bidirectional"))
      (node (ref "R11") (pin "1") (pinfunction "1_1") (pintype "passive"))
      (node (ref "TH3") (pin "2") (pinfunction "2_2") (pintype "passive"))
    )
    (net (code "30") (name "Net-(IC2-AIN2)") (class "Default")
      (node (ref "IC2") (pin "10") (pinfunction "AIN2_10") (pintype "bidirectional"))
      (node (ref "R9") (pin "1") (pinfunction "1_1") (pintype "passive"))
      (node (ref "TH2") (pin "2") (pinfunction "2_2") (pintype "passive"))
    )
    (net (code "31") (name "Net-(IC2-CELL1)") (class "Default")
      (node (ref "C3") (pin "1") (pinfunction "1_1") (pintype "passive"))
      (node (ref "IC2") (pin "1") (pinfunction "REG3_1") (pintype "bidirectional"))
      (node (ref "IC2") (pin "13") (pinfunction "CELLX_13") (pintype "bidirectional"))
      (node (ref "IC2") (pin "5") (pinfunction "VBATT_5") (pintype "bidirectional"))
      (node (ref "IC2") (pin "6") (pinfunction "CELL2_6") (pintype "bidirectional"))
      (node (ref "IC2") (pin "7") (pinfunction "CELL1_7") (pintype "bidirectional"))
      (node (ref "R10") (pin "1") (pinfunction "1_1") (pintype "passive"))
    )
    (net (code "32") (name "Net-(IC2-REG2)") (class "Default")
      (node (ref "C4") (pin "1") (pinfunction "1_1") (pintype "passive"))
      (node (ref "IC2") (pin "3") (pinfunction "REG2_3") (pintype "bidirectional"))
    )
    (net (code "33") (name "Net-(IC2-THRM)") (class "Default")
      (node (ref "IC2") (pin "14") (pinfunction "THRM_14") (pintype "bidirectional"))
      (node (ref "R11") (pin "2") (pinfunction "2_2") (pintype "passive"))
      (node (ref "R9") (pin "2") (pinfunction "2_2") (pintype "passive"))
    )
    (net (code "34") (name "Net-(IC4-BOOST)") (class "Default")
      (node (ref "C6") (pin "1") (pinfunction "1_1") (pintype "passive"))
      (node (ref "IC4") (pin "11") (pinfunction "BOOST_11") (pintype "bidirectional"))
    )
    (net (code "35") (name "Net-(IC4-NTC)") (class "Default")
      (node (ref "IC4") (pin "8") (pinfunction "NTC_8") (pintype "bidirectional"))
      (node (ref "R16") (pin "1") (pinfunction "1_1") (pintype "passive"))
    )
    (net (code "36") (name "Net-(IC4-SENSE)") (class "Default")
      (node (ref "IC4") (pin "10") (pinfunction "SENSE_10") (pintype "bidirectional"))
      (node (ref "L2") (pin "2") (pinfunction "2_2") (pintype "bidirectional"))
      (node (ref "R14") (pin "1") (pinfunction "1_1") (pintype "bidirectional"))
    )
    (net (code "37") (name "Net-(IC4-VFB)") (class "Default")
      (node (ref "IC4") (pin "7") (pinfunction "VFB_7") (pintype "bidirectional"))
      (node (ref "R21") (pin "1") (pinfunction "1_1") (pintype "passive"))
    )
    (net (code "38") (name "Net-(IC4-VIN_REG)") (class "Default")
      (node (ref "IC4") (pin "2") (pinfunction "VIN_REG_2") (pintype "bidirectional"))
      (node (ref "IC5") (pin "6") (pinfunction "V-_6") (pintype "bidirectional"))
      (node (ref "R22") (pin "2") (pinfunction "2_2") (pintype "passive"))
      (node (ref "R23") (pin "1") (pinfunction "1_1") (pintype "passive"))
      (node (ref "R24") (pin "1") (pinfunction "1_1") (pintype "passive"))
    )
    (net (code "39") (name "Net-(IC5-ADJ)") (class "Default")
      (node (ref "IC5") (pin "1") (pinfunction "ADJ_1") (pintype "bidirectional"))
      (node (ref "R24") (pin "2") (pinfunction "2_2") (pintype "passive"))
    )
    (net (code "40") (name "Net-(IC6-EN)") (class "Default")
      (node (ref "EN1") (pin "1") (pinfunction "1_1") (pintype "passive"))
      (node (ref "IC6") (pin "11") (pinfunction "EN_11") (pintype "bidirectional"))
      (node (ref "IC7") (pin "1") (pinfunction "~{RESET}_1") (pintype "bidirectional"))
    )
    (net (code "41") (name "Net-(IC6-SW_1)") (class "Default")
      (node (ref "IC6") (pin "3") (pinfunction "SW_1_3") (pintype "bidirectional"))
      (node (ref "IC6") (pin "4") (pinfunction "SW_2_4") (pintype "bidirectional"))
      (node (ref "L3") (pin "2") (pinfunction "2_2") (pintype "bidirectional"))
    )
    (net (code "42") (name "Net-(IC12-3V3OUT)") (class "Default")
      (node (ref "C24") (pin "1") (pinfunction "1_1") (pintype "passive"))
      (node (ref "IC12") (pin "17") (pinfunction "3V3OUT_17") (pintype "bidirectional"))
    )
    (net (code "43") (name "Net-(IC12-RESET#)") (class "Default")
      (node (ref "IC12") (pin "19") (pinfunction "RESET#_19") (pintype "bidirectional"))
      (node (ref "R19") (pin "1") (pinfunction "1_1") (pintype "passive"))
      (node (ref "R25") (pin "2") (pinfunction "2_2") (pintype "passive"))
    )
    (net (code "44") (name "Net-(Q2-D_1)") (class "Default")
      (node (ref "Q2") (pin "5") (pinfunction "D_1_5") (pintype "bidirectional"))
      (node (ref "Q2") (pin "6") (pinfunction "D_2_6") (pintype "bidirectional"))
      (node (ref "Q2") (pin "7") (pinfunction "D_3_7") (pintype "bidirectional"))
      (node (ref "Q2") (pin "8") (pinfunction "D_4_8") (pintype "bidirectional"))
      (node (ref "R1") (pin "2") (pinfunction "2_2") (pintype "passive"))
      (node (ref "R2") (pin "2") (pinfunction "2_2") (pintype "passive"))
    )
    (net (code "45") (name "Net-(Q2-G)") (class "Default")
      (node (ref "Q2") (pin "4") (pinfunction "G_4") (pintype "bidirectional"))
      (node (ref "R26") (pin "2") (pinfunction "2_2") (pintype "passive"))
      (node (ref "R5") (pin "2") (pinfunction "2_2") (pintype "passive"))
    )
    (net (code "46") (name "Net-(Q3-B)") (class "Default")
      (node (ref "Q3") (pin "1") (pinfunction "B_1") (pintype "bidirectional"))
      (node (ref "R6") (pin "2") (pinfunction "2_2") (pintype "passive"))
    )
    (net (code "47") (name "Net-(Q4-B)") (class "Default")
      (node (ref "Q4") (pin "1") (pinfunction "B_1") (pintype "bidirectional"))
      (node (ref "R13") (pin "2") (pinfunction "2_2") (pintype "passive"))
    )
    (net (code "48") (name "Net-(R16-Pad2)") (class "Default")
      (node (ref "R16") (pin "2") (pinfunction "2_2") (pintype "passive"))
      (node (ref "TH1") (pin "2") (pinfunction "2_2") (pintype "passive"))
    )
    (net (code "49") (name "Net-(R18-Pad2)") (class "Default")
      (node (ref "R18") (pin "2") (pinfunction "2_2") (pintype "passive"))
      (node (ref "R20") (pin "1") (pinfunction "1_1") (pintype "passive"))
      (node (ref "R21") (pin "2") (pinfunction "2_2") (pintype "passive"))
    )
    (net (code "50") (name "PACK") (class "Default")
      (node (ref "C11") (pin "1") (pinfunction "1_1") (pintype "passive"))
      (node (ref "C5") (pin "1") (pinfunction "1_1") (pintype "passive"))
      (node (ref "EN1") (pin "2") (pinfunction "2_2") (pintype "passive"))
      (node (ref "F2") (pin "2") (pinfunction "2_2") (pintype "bidirectional"))
      (node (ref "IC3") (pin "3") (pinfunction "INPUT_3") (pintype "input"))
      (node (ref "IC6") (pin "8") (pinfunction "VBAT_8") (pintype "bidirectional"))
      (node (ref "IC7") (pin "3") (pinfunction "VDD_3") (pintype "bidirectional"))
      (node (ref "L3") (pin "1") (pinfunction "1_1") (pintype "bidirectional"))
      (node (ref "R1") (pin "1") (pinfunction "1_1") (pintype "passive"))
      (node (ref "R10") (pin "2") (pinfunction "2_2") (pintype "passive"))
      (node (ref "R2") (pin "1") (pinfunction "1_1") (pintype "passive"))
      (node (ref "U$2") (pin "P$1") (pinfunction "P$1_P$1") (pintype "bidirectional"))
      (node (ref "U$2") (pin "P$3") (pinfunction "P$3_P$3") (pintype "bidirectional"))
      (node (ref "U$2") (pin "P$5") (pinfunction "P$5_P$5") (pintype "bidirectional"))
      (node (ref "U$3") (pin "P$2") (pinfunction "P$2_P$2") (pintype "bidirectional"))
      (node (ref "U$3") (pin "P$4") (pinfunction "P$4_P$4") (pintype "bidirectional"))
    )
    (net (code "51") (name "PWM") (class "Default")
      (node (ref "IC10") (pin "13") (pinfunction "IO14_13") (pintype "bidirectional"))
      (node (ref "R5") (pin "1") (pinfunction "1_1") (pintype "passive"))
    )
    (net (code "52") (name "S") (class "Default")
      (node (ref "IC10") (pin "21") (pinfunction "SDO/SD0_21") (pintype "bidirectional"))
      (node (ref "IC8") (pin "8") (pinfunction "S_8") (pintype "bidirectional"))
    )
    (net (code "53") (name "SCL") (class "Default")
      (node (ref "IC10") (pin "36") (pinfunction "IO22_36") (pintype "bidirectional"))
      (node (ref "IC2") (pin "11") (pinfunction "OD/SCL_11") (pintype "bidirectional"))
    )
    (net (code "54") (name "SDA") (class "Default")
      (node (ref "IC10") (pin "33") (pinfunction "IO21_33") (pintype "bidirectional"))
      (node (ref "IC2") (pin "12") (pinfunction "DQ/SDA_12") (pintype "bidirectional"))
    )
    (net (code "55") (name "SHDN") (class "Default")
      (node (ref "IC10") (pin "22") (pinfunction "SDI/SD1_22") (pintype "bidirectional"))
      (node (ref "IC8") (pin "5") (pinfunction "SHDN_5") (pintype "bidirectional"))
    )
    (net (code "56") (name "SOL") (class "Default")
      (node (ref "D6") (pin "2") (pinfunction "A_2") (pintype "bidirectional"))
      (node (ref "U$4") (pin "P$4") (pinfunction "P$4_P$4") (pintype "bidirectional"))
    )
    (net (code "57") (name "USB_CONN_V+") (class "Default")
      (node (ref "R19") (pin "2") (pinfunction "2_2") (pintype "passive"))
    )
    (net (code "58") (name "V+") (class "Default")
      (node (ref "C2") (pin "1") (pinfunction "1_1") (pintype "passive"))
      (node (ref "IC9") (pin "5") (pinfunction "VCC_5") (pintype "bidirectional"))
      (node (ref "J1") (pin "1") (pinfunction "1_1") (pintype "bidirectional"))
    )
    (net (code "59") (name "unconnected-(IC5-NC-Pad2)") (class "Default")
      (node (ref "IC5") (pin "2") (pinfunction "NC_2") (pintype "no_connect"))
    )
    (net (code "60") (name "unconnected-(IC5-NC1-Pad3)") (class "Default")
      (node (ref "IC5") (pin "3") (pinfunction "NC1_3") (pintype "bidirectional"))
    )
    (net (code "61") (name "unconnected-(IC5-NC2-Pad5)") (class "Default")
      (node (ref "IC5") (pin "5") (pinfunction "NC2_5") (pintype "bidirectional"))
    )
    (net (code "62") (name "unconnected-(IC5-NC3-Pad7)") (class "Default")
      (node (ref "IC5") (pin "7") (pinfunction "NC3_7") (pintype "bidirectional"))
    )
    (net (code "63") (name "unconnected-(IC5-NC4-Pad8)") (class "Default")
      (node (ref "IC5") (pin "8") (pinfunction "NC4_8") (pintype "bidirectional"))
    )
    (net (code "64") (name "unconnected-(IC6-FB-Pad14)") (class "Default")
      (node (ref "IC6") (pin "14") (pinfunction "FB_14") (pintype "bidirectional"))
    )
    (net (code "65") (name "unconnected-(IC6-LBO-Pad12)") (class "Default")
      (node (ref "IC6") (pin "12") (pinfunction "LBO_12") (pintype "bidirectional"))
    )
    (net (code "66") (name "unconnected-(IC6-NC-Pad2)") (class "Default")
      (node (ref "IC6") (pin "2") (pinfunction "NC_2") (pintype "no_connect"))
    )
    (net (code "67") (name "unconnected-(IC10-IO2-Pad24)") (class "Default")
      (node (ref "IC10") (pin "24") (pinfunction "IO2_24") (pintype "bidirectional"))
    )
    (net (code "68") (name "unconnected-(IC10-IO12-Pad14)") (class "Default")
      (node (ref "IC10") (pin "14") (pinfunction "IO12_14") (pintype "bidirectional"))
    )
    (net (code "69") (name "unconnected-(IC10-IO13-Pad16)") (class "Default")
      (node (ref "IC10") (pin "16") (pinfunction "IO13_16") (pintype "bidirectional"))
    )
    (net (code "70") (name "unconnected-(IC10-IO15-Pad23)") (class "Default")
      (node (ref "IC10") (pin "23") (pinfunction "IO15_23") (pintype "bidirectional"))
    )
    (net (code "71") (name "unconnected-(IC10-IO16-Pad27)") (class "Default")
      (node (ref "IC10") (pin "27") (pinfunction "IO16_27") (pintype "bidirectional"))
    )
    (net (code "72") (name "unconnected-(IC10-IO17-Pad28)") (class "Default")
      (node (ref "IC10") (pin "28") (pinfunction "IO17_28") (pintype "bidirectional"))
    )
    (net (code "73") (name "unconnected-(IC10-IO18-Pad30)") (class "Default")
      (node (ref "IC10") (pin "30") (pinfunction "IO18_30") (pintype "bidirectional"))
    )
    (net (code "74") (name "unconnected-(IC10-IO19-Pad31)") (class "Default")
      (node (ref "IC10") (pin "31") (pinfunction "IO19_31") (pintype "bidirectional"))
    )
    (net (code "75") (name "unconnected-(IC10-IO23-Pad37)") (class "Default")
      (node (ref "IC10") (pin "37") (pinfunction "IO23_37") (pintype "bidirectional"))
    )
    (net (code "76") (name "unconnected-(IC10-IO25-Pad10)") (class "Default")
      (node (ref "IC10") (pin "10") (pinfunction "IO25_10") (pintype "bidirectional"))
    )
    (net (code "77") (name "unconnected-(IC10-IO27-Pad12)") (class "Default")
      (node (ref "IC10") (pin "12") (pinfunction "IO27_12") (pintype "bidirectional"))
    )
    (net (code "78") (name "unconnected-(IC10-IO32-Pad8)") (class "Default")
      (node (ref "IC10") (pin "8") (pinfunction "IO32_8") (pintype "bidirectional"))
    )
    (net (code "79") (name "unconnected-(IC10-IO33-Pad9)") (class "Default")
      (node (ref "IC10") (pin "9") (pinfunction "IO33_9") (pintype "bidirectional"))
    )
    (net (code "80") (name "unconnected-(IC10-NC-Pad32)") (class "Default")
      (node (ref "IC10") (pin "32") (pinfunction "NC_32") (pintype "no_connect"))
    )
    (net (code "81") (name "unconnected-(IC10-SCK{slash}CLK-Pad20)") (class "Default")
      (node (ref "IC10") (pin "20") (pinfunction "SCK/CLK_20") (pintype "bidirectional"))
    )
    (net (code "82") (name "unconnected-(IC10-SCS{slash}CMD-Pad19)") (class "Default")
      (node (ref "IC10") (pin "19") (pinfunction "SCS/CMD_19") (pintype "bidirectional"))
    )
    (net (code "83") (name "unconnected-(IC10-SHD{slash}SD2-Pad17)") (class "Default")
      (node (ref "IC10") (pin "17") (pinfunction "SHD/SD2_17") (pintype "bidirectional"))
    )
    (net (code "84") (name "unconnected-(IC10-SWP{slash}SD3-Pad18)") (class "Default")
      (node (ref "IC10") (pin "18") (pinfunction "SWP/SD3_18") (pintype "bidirectional"))
    )
    (net (code "85") (name "unconnected-(IC12-CBUS2-Pad13)") (class "Default")
      (node (ref "IC12") (pin "13") (pinfunction "CBUS2_13") (pintype "bidirectional"))
    )
    (net (code "86") (name "unconnected-(IC12-CBUS3-Pad14)") (class "Default")
      (node (ref "IC12") (pin "14") (pinfunction "CBUS3_14") (pintype "bidirectional"))
    )
    (net (code "87") (name "unconnected-(IC12-CBUS4-Pad12)") (class "Default")
      (node (ref "IC12") (pin "12") (pinfunction "CBUS4_12") (pintype "bidirectional"))
    )
    (net (code "88") (name "unconnected-(IC12-CTS#-Pad11)") (class "Default")
      (node (ref "IC12") (pin "11") (pinfunction "CTS#_11") (pintype "bidirectional"))
    )
    (net (code "89") (name "unconnected-(IC12-DCD#-Pad10)") (class "Default")
      (node (ref "IC12") (pin "10") (pinfunction "DCD#_10") (pintype "bidirectional"))
    )
    (net (code "90") (name "unconnected-(IC12-DSR#-Pad9)") (class "Default")
      (node (ref "IC12") (pin "9") (pinfunction "DSR#_9") (pintype "bidirectional"))
    )
    (net (code "91") (name "unconnected-(IC12-NC_1-Pad8)") (class "Default")
      (node (ref "IC12") (pin "8") (pinfunction "NC_1_8") (pintype "bidirectional"))
    )
    (net (code "92") (name "unconnected-(IC12-NC_2-Pad24)") (class "Default")
      (node (ref "IC12") (pin "24") (pinfunction "NC_2_24") (pintype "bidirectional"))
    )
    (net (code "93") (name "unconnected-(IC12-OSCI-Pad27)") (class "Default")
      (node (ref "IC12") (pin "27") (pinfunction "OSCI_27") (pintype "bidirectional"))
    )
    (net (code "94") (name "unconnected-(IC12-OSCO-Pad28)") (class "Default")
      (node (ref "IC12") (pin "28") (pinfunction "OSCO_28") (pintype "bidirectional"))
    )
    (net (code "95") (name "unconnected-(IC12-RI#-Pad6)") (class "Default")
      (node (ref "IC12") (pin "6") (pinfunction "RI#_6") (pintype "bidirectional"))
    )
    (net (code "96") (name "unconnected-(J1-Pad5)") (class "Default")
      (node (ref "J1") (pin "5") (pinfunction "5_5") (pintype "bidirectional"))
    )
    (net (code "97") (name "unconnected-(J1-PadMP1)") (class "Default")
      (node (ref "J1") (pin "MP1") (pinfunction "MP1_MP1") (pintype "bidirectional"))
    )
    (net (code "98") (name "unconnected-(J1-PadMP2)") (class "Default")
      (node (ref "J1") (pin "MP2") (pinfunction "MP2_MP2") (pintype "bidirectional"))
    )
    (net (code "99") (name "unconnected-(J1-PadMP3)") (class "Default")
      (node (ref "J1") (pin "MP3") (pinfunction "MP3_MP3") (pintype "bidirectional"))
    )
    (net (code "100") (name "unconnected-(J1-PadMP4)") (class "Default")
      (node (ref "J1") (pin "MP4") (pinfunction "MP4_MP4") (pintype "bidirectional"))
    )
    (net (code "101") (name "unconnected-(R7-C-Pad2)") (class "Default")
      (node (ref "R7") (pin "2") (pinfunction "C_2") (pintype "passive"))
    )
    (net (code "102") (name "unconnected-(R8-C-Pad2)") (class "Default")
      (node (ref "R8") (pin "2") (pinfunction "C_2") (pintype "passive"))
    )
    (net (code "103") (name "unconnected-(Z2-NC-Pad2)") (class "Default")
      (node (ref "Z2") (pin "2") (pinfunction "NC_2") (pintype "no_connect"))
    )
  )
)
